# MBT42Q_CR2032_v01.net
KiCad netlist of a schematic drawn in EAGLE
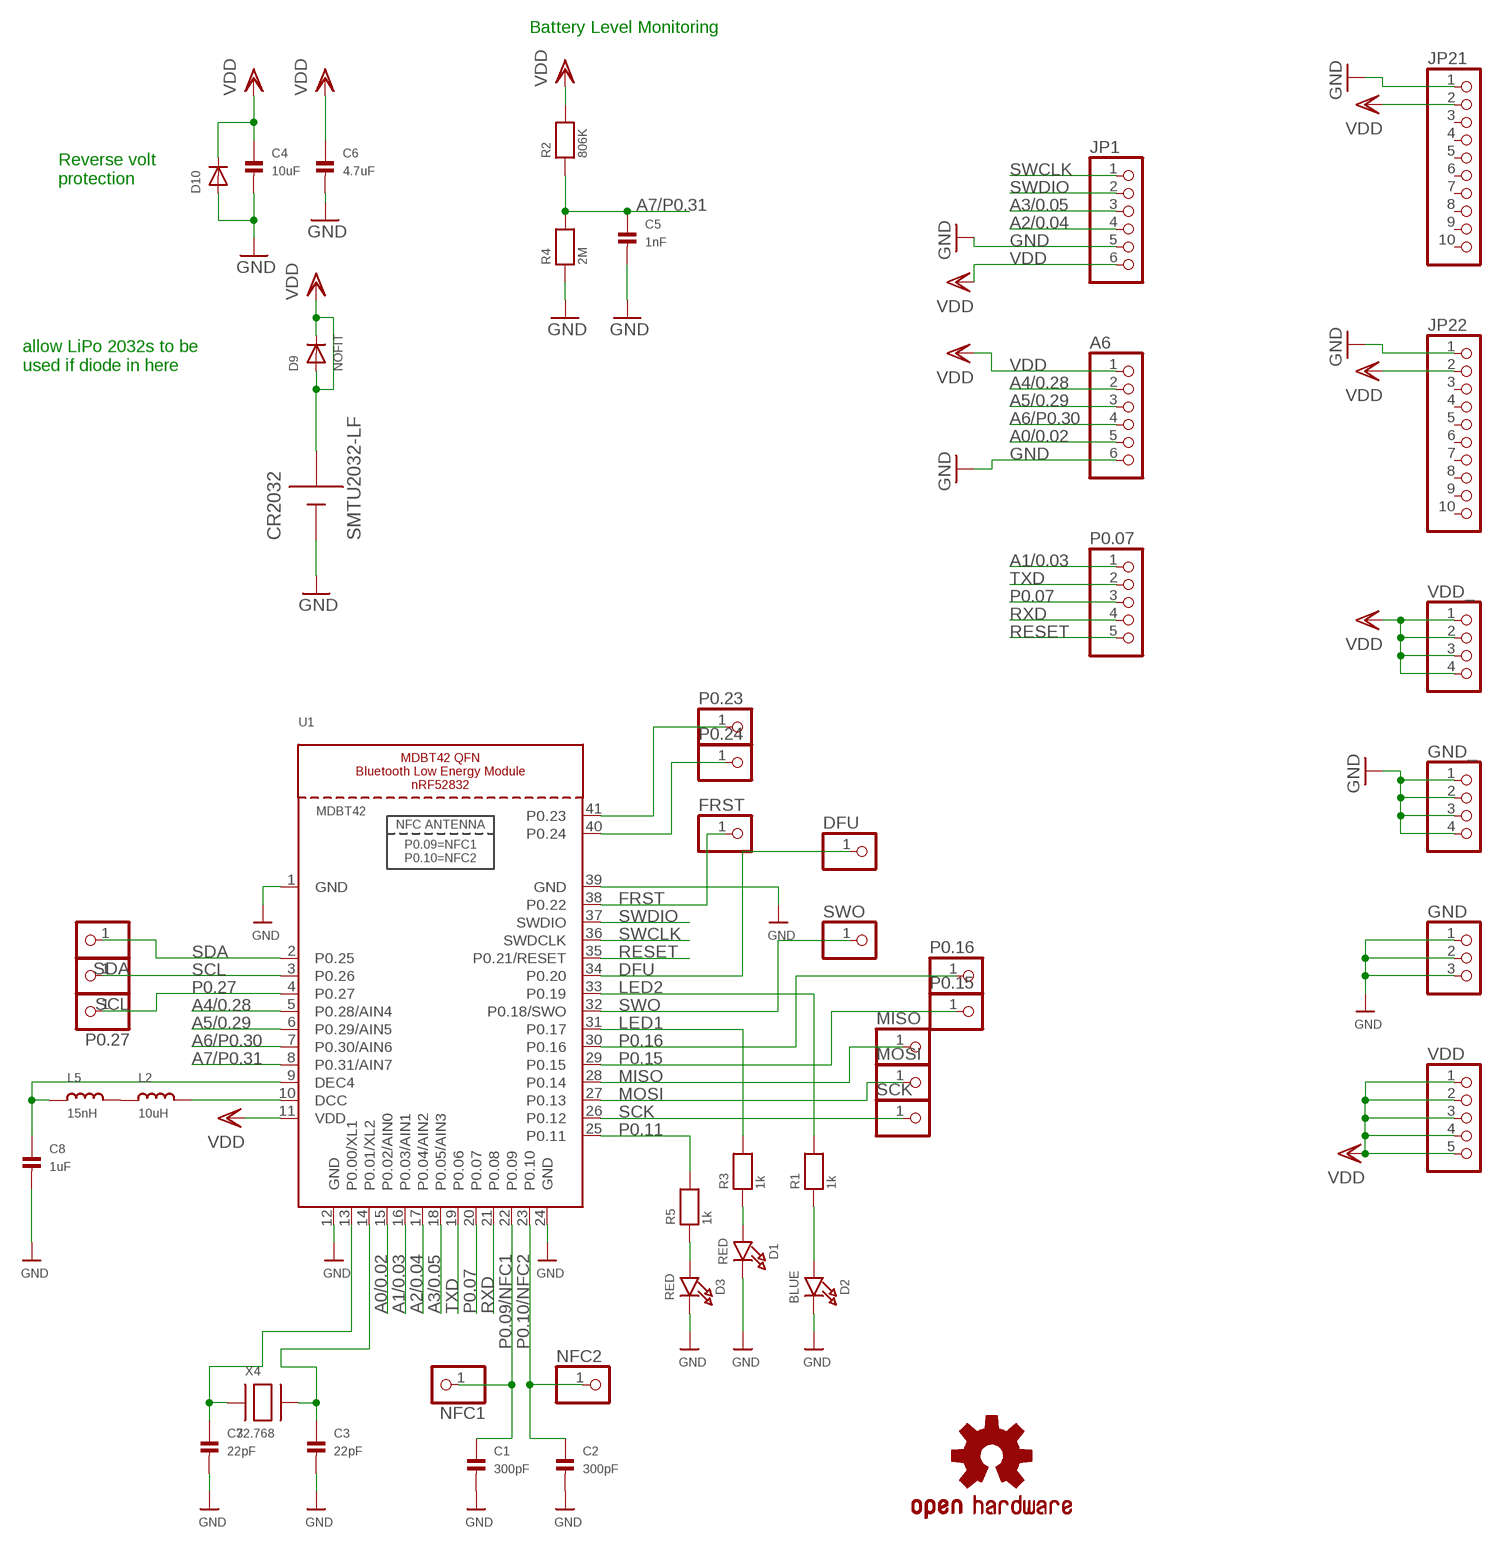
[diagram p0: schematic, sheet 1]

(export (version "E")
  (design (tool "Eeschema 10.0.6"))
  (components
    (comp (ref "A6")
      (value "HEADER-1X6ROUND")
      (footprint "eagle-import:1X06_ROUND")
      (libsource (lib "eagle-import") (part "HEADER-1X6ROUND"))
    )
    (comp (ref "C1")
      (value "300pF")
      (footprint "eagle-import:0805")
      (libsource (lib "eagle-import") (part "CAP_CERAMIC0805"))
    )
    (comp (ref "C2")
      (value "300pF")
      (footprint "eagle-import:0805")
      (libsource (lib "eagle-import") (part "CAP_CERAMIC0805"))
    )
    (comp (ref "C3")
      (value "22pF")
      (footprint "eagle-import:0805")
      (libsource (lib "eagle-import") (part "CAP_CERAMIC0805"))
    )
    (comp (ref "C4")
      (value "10uF")
      (footprint "eagle-import:0805")
      (libsource (lib "eagle-import") (part "CAP_CERAMIC0805"))
    )
    (comp (ref "C5")
      (value "1nF")
      (footprint "eagle-import:0805")
      (libsource (lib "eagle-import") (part "CAP_CERAMIC0805"))
    )
    (comp (ref "C6")
      (value "4.7uF")
      (footprint "eagle-import:0805")
      (libsource (lib "eagle-import") (part "CAP_CERAMIC0805"))
    )
    (comp (ref "C7")
      (value "22pF")
      (footprint "eagle-import:0805")
      (libsource (lib "eagle-import") (part "CAP_CERAMIC0805"))
    )
    (comp (ref "C8")
      (value "1uF")
      (footprint "eagle-import:0805")
      (libsource (lib "eagle-import") (part "CAP_CERAMIC0805"))
    )
    (comp (ref "CR2032")
      (value "SMTU2032-LF")
      (footprint "eagle-import:SMTU2032-LF")
      (libsource (lib "eagle-import") (part "SMTU2032-LF"))
    )
    (comp (ref "D1")
      (value "RED")
      (footprint "eagle-import:CHIPLED_0805_NOOUTLINE")
      (libsource (lib "eagle-import") (part "LED0805_NOOUTLINE"))
    )
    (comp (ref "D2")
      (value "BLUE")
      (footprint "eagle-import:CHIPLED_0805_NOOUTLINE")
      (libsource (lib "eagle-import") (part "LED0805_NOOUTLINE"))
    )
    (comp (ref "D3")
      (value "RED")
      (footprint "eagle-import:CHIPLED_0805_NOOUTLINE")
      (libsource (lib "eagle-import") (part "LED0805_NOOUTLINE"))
    )
    (comp (ref "D9")
      (value "NOFIT")
      (footprint "eagle-import:SOD-523")
      (libsource (lib "eagle-import") (part "DIODESOD-523"))
    )
    (comp (ref "D10")
      (value "DIODESOD-523")
      (footprint "eagle-import:SOD-523")
      (libsource (lib "eagle-import") (part "DIODESOD-523"))
    )
    (comp (ref "DFU")
      (value "HEADER-1X1ROUND")
      (footprint "eagle-import:1X01_ROUND")
      (libsource (lib "eagle-import") (part "HEADER-1X1ROUND"))
    )
    (comp (ref "FRST")
      (value "HEADER-1X1ROUND")
      (footprint "eagle-import:1X01_ROUND")
      (libsource (lib "eagle-import") (part "HEADER-1X1ROUND"))
    )
    (comp (ref "GND")
      (value "HEADER-1X3ROUND")
      (footprint "eagle-import:1X03_ROUND")
      (libsource (lib "eagle-import") (part "HEADER-1X3ROUND"))
    )
    (comp (ref "GND_")
      (value "HEADER-1X4ROUND")
      (footprint "eagle-import:1X04_ROUND")
      (libsource (lib "eagle-import") (part "HEADER-1X4ROUND"))
    )
    (comp (ref "JP1")
      (value "HEADER-1X6ROUND")
      (footprint "eagle-import:1X06_ROUND")
      (libsource (lib "eagle-import") (part "HEADER-1X6ROUND"))
    )
    (comp (ref "JP21")
      (value "HEADER-1X10ROUND")
      (footprint "eagle-import:1X10_ROUND")
      (libsource (lib "eagle-import") (part "HEADER-1X10ROUND"))
    )
    (comp (ref "JP22")
      (value "HEADER-1X10ROUND")
      (footprint "eagle-import:1X10_ROUND")
      (libsource (lib "eagle-import") (part "HEADER-1X10ROUND"))
    )
    (comp (ref "L2")
      (value "10uH")
      (footprint "eagle-import:_0805")
      (libsource (lib "eagle-import") (part "INDUCTOR_0805"))
    )
    (comp (ref "L5")
      (value "15nH")
      (footprint "eagle-import:_0805")
      (libsource (lib "eagle-import") (part "INDUCTOR_0805"))
    )
    (comp (ref "LOGO1")
      (value "OSHW-LOGOS")
      (footprint "eagle-import:OSHW-LOGO-S")
      (libsource (lib "eagle-import") (part "OSHW-LOGOS"))
    )
    (comp (ref "MISO")
      (value "HEADER-1X1ROUND")
      (footprint "eagle-import:1X01_ROUND")
      (libsource (lib "eagle-import") (part "HEADER-1X1ROUND"))
    )
    (comp (ref "MOSI")
      (value "HEADER-1X1ROUND")
      (footprint "eagle-import:1X01_ROUND")
      (libsource (lib "eagle-import") (part "HEADER-1X1ROUND"))
    )
    (comp (ref "NFC1")
      (value "HEADER-1X1ROUND")
      (footprint "eagle-import:1X01_ROUND")
      (libsource (lib "eagle-import") (part "HEADER-1X1ROUND"))
    )
    (comp (ref "NFC2")
      (value "HEADER-1X1ROUND")
      (footprint "eagle-import:1X01_ROUND")
      (libsource (lib "eagle-import") (part "HEADER-1X1ROUND"))
    )
    (comp (ref "P0.07")
      (value "HEADER-1X5ROUND")
      (footprint "eagle-import:1X05_ROUND")
      (libsource (lib "eagle-import") (part "HEADER-1X5ROUND"))
    )
    (comp (ref "P0.15")
      (value "HEADER-1X1ROUND")
      (footprint "eagle-import:1X01_ROUND")
      (libsource (lib "eagle-import") (part "HEADER-1X1ROUND"))
    )
    (comp (ref "P0.16")
      (value "HEADER-1X1ROUND")
      (footprint "eagle-import:1X01_ROUND")
      (libsource (lib "eagle-import") (part "HEADER-1X1ROUND"))
    )
    (comp (ref "P0.23")
      (value "HEADER-1X1ROUND")
      (footprint "eagle-import:1X01_ROUND")
      (libsource (lib "eagle-import") (part "HEADER-1X1ROUND"))
    )
    (comp (ref "P0.24")
      (value "HEADER-1X1ROUND")
      (footprint "eagle-import:1X01_ROUND")
      (libsource (lib "eagle-import") (part "HEADER-1X1ROUND"))
    )
    (comp (ref "P0.27")
      (value "HEADER-1X1ROUND")
      (footprint "eagle-import:1X01_ROUND")
      (libsource (lib "eagle-import") (part "HEADER-1X1ROUND"))
    )
    (comp (ref "R1")
      (value "1k")
      (footprint "eagle-import:0805")
      (libsource (lib "eagle-import") (part "RESISTOR0805"))
    )
    (comp (ref "R2")
      (value "806K")
      (footprint "eagle-import:0805")
      (libsource (lib "eagle-import") (part "RESISTOR0805"))
    )
    (comp (ref "R3")
      (value "1k")
      (footprint "eagle-import:0805")
      (libsource (lib "eagle-import") (part "RESISTOR0805"))
    )
    (comp (ref "R4")
      (value "2M")
      (footprint "eagle-import:0805")
      (libsource (lib "eagle-import") (part "RESISTOR0805"))
    )
    (comp (ref "R5")
      (value "1k")
      (footprint "eagle-import:0805")
      (libsource (lib "eagle-import") (part "RESISTOR0805"))
    )
    (comp (ref "SCK")
      (value "HEADER-1X1ROUND")
      (footprint "eagle-import:1X01_ROUND")
      (libsource (lib "eagle-import") (part "HEADER-1X1ROUND"))
    )
    (comp (ref "SCL")
      (value "HEADER-1X1ROUND")
      (footprint "eagle-import:1X01_ROUND")
      (libsource (lib "eagle-import") (part "HEADER-1X1ROUND"))
    )
    (comp (ref "SDA")
      (value "HEADER-1X1ROUND")
      (footprint "eagle-import:1X01_ROUND")
      (libsource (lib "eagle-import") (part "HEADER-1X1ROUND"))
    )
    (comp (ref "SWO")
      (value "HEADER-1X1ROUND")
      (footprint "eagle-import:1X01_ROUND")
      (libsource (lib "eagle-import") (part "HEADER-1X1ROUND"))
    )
    (comp (ref "U1")
      (value "MDBT42")
      (footprint "eagle-import:BLE_MODULE_RAYTAC_MDBT42")
      (libsource (lib "eagle-import") (part "NRF52832_MODULE_MDBT42"))
    )
    (comp (ref "VDD")
      (value "HEADER-1X5ROUND")
      (footprint "eagle-import:1X05_ROUND")
      (libsource (lib "eagle-import") (part "HEADER-1X5ROUND"))
    )
    (comp (ref "VDD_")
      (value "HEADER-1X4ROUND")
      (footprint "eagle-import:1X04_ROUND")
      (libsource (lib "eagle-import") (part "HEADER-1X4ROUND"))
    )
    (comp (ref "X4")
      (value "32.768")
      (footprint "eagle-import:XTAL3215")
      (libsource (lib "eagle-import") (part "XTAL-3.2X1.5"))
    )
  )
  (nets
    (net (code "1") (name "/A0{slash}0.02") (class "Default")
      (node (ref "A6") (pin "5") (pinfunction "5_5") (pintype "passive"))
      (node (ref "U1") (pin "15") (pinfunction "P0.02/AIN0_15") (pintype "bidirectional"))
    )
    (net (code "2") (name "/A1{slash}0.03") (class "Default")
      (node (ref "P0.07") (pin "1") (pinfunction "1_1") (pintype "passive"))
      (node (ref "U1") (pin "16") (pinfunction "P0.03/AIN1_16") (pintype "bidirectional"))
    )
    (net (code "3") (name "/A2{slash}0.04") (class "Default")
      (node (ref "JP1") (pin "4") (pinfunction "4_4") (pintype "passive"))
      (node (ref "U1") (pin "17") (pinfunction "P0.04/AIN2_17") (pintype "bidirectional"))
    )
    (net (code "4") (name "/A3{slash}0.05") (class "Default")
      (node (ref "JP1") (pin "3") (pinfunction "3_3") (pintype "passive"))
      (node (ref "U1") (pin "18") (pinfunction "P0.05/AIN3_18") (pintype "bidirectional"))
    )
    (net (code "5") (name "/A4{slash}0.28") (class "Default")
      (node (ref "A6") (pin "2") (pinfunction "2_2") (pintype "passive"))
      (node (ref "U1") (pin "5") (pinfunction "P0.28/AIN4_5") (pintype "bidirectional"))
    )
    (net (code "6") (name "/A5{slash}0.29") (class "Default")
      (node (ref "A6") (pin "3") (pinfunction "3_3") (pintype "passive"))
      (node (ref "U1") (pin "6") (pinfunction "P0.29/AIN5_6") (pintype "bidirectional"))
    )
    (net (code "7") (name "/A6{slash}P0.30") (class "Default")
      (node (ref "A6") (pin "4") (pinfunction "4_4") (pintype "passive"))
      (node (ref "U1") (pin "7") (pinfunction "P0.30/AIN6_7") (pintype "bidirectional"))
    )
    (net (code "8") (name "/A7{slash}P0.31") (class "Default")
      (node (ref "C5") (pin "1") (pinfunction "P$1_1") (pintype "passive"))
      (node (ref "R2") (pin "1") (pinfunction "1_1") (pintype "passive"))
      (node (ref "R4") (pin "2") (pinfunction "2_2") (pintype "passive"))
      (node (ref "U1") (pin "8") (pinfunction "P0.31/AIN7_8") (pintype "bidirectional"))
    )
    (net (code "9") (name "/DFU") (class "Default")
      (node (ref "DFU") (pin "1") (pinfunction "1_1") (pintype "passive"))
      (node (ref "U1") (pin "34") (pinfunction "P0.20_34") (pintype "bidirectional"))
    )
    (net (code "10") (name "/FRST") (class "Default")
      (node (ref "FRST") (pin "1") (pinfunction "1_1") (pintype "passive"))
      (node (ref "U1") (pin "38") (pinfunction "P0.22_38") (pintype "bidirectional"))
    )
    (net (code "11") (name "/LED1") (class "Default")
      (node (ref "R3") (pin "2") (pinfunction "2_2") (pintype "passive"))
      (node (ref "U1") (pin "31") (pinfunction "P0.17_31") (pintype "bidirectional"))
    )
    (net (code "12") (name "/LED2") (class "Default")
      (node (ref "R1") (pin "2") (pinfunction "2_2") (pintype "passive"))
      (node (ref "U1") (pin "33") (pinfunction "P0.19_33") (pintype "bidirectional"))
    )
    (net (code "13") (name "/MISO") (class "Default")
      (node (ref "MISO") (pin "1") (pinfunction "1_1") (pintype "passive"))
      (node (ref "U1") (pin "28") (pinfunction "P0.14_28") (pintype "bidirectional"))
    )
    (net (code "14") (name "/MOSI") (class "Default")
      (node (ref "MOSI") (pin "1") (pinfunction "1_1") (pintype "passive"))
      (node (ref "U1") (pin "27") (pinfunction "P0.13_27") (pintype "bidirectional"))
    )
    (net (code "15") (name "/P0.07") (class "Default")
      (node (ref "P0.07") (pin "3") (pinfunction "3_3") (pintype "passive"))
      (node (ref "U1") (pin "20") (pinfunction "P0.07_20") (pintype "bidirectional"))
    )
    (net (code "16") (name "/P0.09{slash}NFC1") (class "Default")
      (node (ref "C1") (pin "1") (pinfunction "P$1_1") (pintype "passive"))
      (node (ref "NFC1") (pin "1") (pinfunction "1_1") (pintype "passive"))
      (node (ref "U1") (pin "22") (pinfunction "P0.09_22") (pintype "bidirectional"))
    )
    (net (code "17") (name "/P0.10{slash}NFC2") (class "Default")
      (node (ref "C2") (pin "1") (pinfunction "P$1_1") (pintype "passive"))
      (node (ref "NFC2") (pin "1") (pinfunction "1_1") (pintype "passive"))
      (node (ref "U1") (pin "23") (pinfunction "P0.10_23") (pintype "bidirectional"))
    )
    (net (code "18") (name "/P0.11") (class "Default")
      (node (ref "R5") (pin "2") (pinfunction "2_2") (pintype "passive"))
      (node (ref "U1") (pin "25") (pinfunction "P0.11_25") (pintype "bidirectional"))
    )
    (net (code "19") (name "/P0.15") (class "Default")
      (node (ref "P0.15") (pin "1") (pinfunction "1_1") (pintype "passive"))
      (node (ref "U1") (pin "29") (pinfunction "P0.15_29") (pintype "bidirectional"))
    )
    (net (code "20") (name "/P0.16") (class "Default")
      (node (ref "P0.16") (pin "1") (pinfunction "1_1") (pintype "passive"))
      (node (ref "U1") (pin "30") (pinfunction "P0.16_30") (pintype "bidirectional"))
    )
    (net (code "21") (name "/P0.27") (class "Default")
      (node (ref "P0.27") (pin "1") (pinfunction "1_1") (pintype "passive"))
      (node (ref "U1") (pin "4") (pinfunction "P0.27_4") (pintype "bidirectional"))
    )
    (net (code "22") (name "/RESET") (class "Default")
      (node (ref "P0.07") (pin "5") (pinfunction "5_5") (pintype "passive"))
      (node (ref "U1") (pin "35") (pinfunction "P0.21/RESET_35") (pintype "bidirectional"))
    )
    (net (code "23") (name "/RXD") (class "Default")
      (node (ref "P0.07") (pin "4") (pinfunction "4_4") (pintype "passive"))
      (node (ref "U1") (pin "21") (pinfunction "P0.08_21") (pintype "bidirectional"))
    )
    (net (code "24") (name "/SCK") (class "Default")
      (node (ref "SCK") (pin "1") (pinfunction "1_1") (pintype "passive"))
      (node (ref "U1") (pin "26") (pinfunction "P0.12_26") (pintype "bidirectional"))
    )
    (net (code "25") (name "/SCL") (class "Default")
      (node (ref "SCL") (pin "1") (pinfunction "1_1") (pintype "passive"))
      (node (ref "U1") (pin "3") (pinfunction "P0.26_3") (pintype "bidirectional"))
    )
    (net (code "26") (name "/SDA") (class "Default")
      (node (ref "SDA") (pin "1") (pinfunction "1_1") (pintype "passive"))
      (node (ref "U1") (pin "2") (pinfunction "P0.25_2") (pintype "bidirectional"))
    )
    (net (code "27") (name "/SWCLK") (class "Default")
      (node (ref "JP1") (pin "1") (pinfunction "1_1") (pintype "passive"))
      (node (ref "U1") (pin "36") (pinfunction "SWDCLK_36") (pintype "bidirectional"))
    )
    (net (code "28") (name "/SWDIO") (class "Default")
      (node (ref "JP1") (pin "2") (pinfunction "2_2") (pintype "passive"))
      (node (ref "U1") (pin "37") (pinfunction "SWDIO_37") (pintype "bidirectional"))
    )
    (net (code "29") (name "/SWO") (class "Default")
      (node (ref "SWO") (pin "1") (pinfunction "1_1") (pintype "passive"))
      (node (ref "U1") (pin "32") (pinfunction "P0.18/SWO_32") (pintype "bidirectional"))
    )
    (net (code "30") (name "/TXD") (class "Default")
      (node (ref "P0.07") (pin "2") (pinfunction "2_2") (pintype "passive"))
      (node (ref "U1") (pin "19") (pinfunction "P0.06_19") (pintype "bidirectional"))
    )
    (net (code "31") (name "GND") (class "Default")
      (node (ref "A6") (pin "6") (pinfunction "6_6") (pintype "passive"))
      (node (ref "C1") (pin "2") (pinfunction "P$2_2") (pintype "passive"))
      (node (ref "C2") (pin "2") (pinfunction "P$2_2") (pintype "passive"))
      (node (ref "C3") (pin "2") (pinfunction "P$2_2") (pintype "passive"))
      (node (ref "C4") (pin "2") (pinfunction "P$2_2") (pintype "passive"))
      (node (ref "C5") (pin "2") (pinfunction "P$2_2") (pintype "passive"))
      (node (ref "C6") (pin "2") (pinfunction "P$2_2") (pintype "passive"))
      (node (ref "C7") (pin "2") (pinfunction "P$2_2") (pintype "passive"))
      (node (ref "C8") (pin "2") (pinfunction "P$2_2") (pintype "passive"))
      (node (ref "CR2032") (pin "P$2") (pinfunction "GND_P$2") (pintype "power_in"))
      (node (ref "D1") (pin "C") (pinfunction "C_C") (pintype "passive"))
      (node (ref "D10") (pin "A") (pinfunction "A_A") (pintype "passive"))
      (node (ref "D2") (pin "C") (pinfunction "C_C") (pintype "passive"))
      (node (ref "D3") (pin "C") (pinfunction "C_C") (pintype "passive"))
      (node (ref "GND") (pin "1") (pinfunction "1_1") (pintype "passive"))
      (node (ref "GND") (pin "2") (pinfunction "2_2") (pintype "passive"))
      (node (ref "GND") (pin "3") (pinfunction "3_3") (pintype "passive"))
      (node (ref "GND_") (pin "1") (pinfunction "1_1") (pintype "passive"))
      (node (ref "GND_") (pin "2") (pinfunction "2_2") (pintype "passive"))
      (node (ref "GND_") (pin "3") (pinfunction "3_3") (pintype "passive"))
      (node (ref "GND_") (pin "4") (pinfunction "4_4") (pintype "passive"))
      (node (ref "JP1") (pin "5") (pinfunction "5_5") (pintype "passive"))
      (node (ref "JP21") (pin "1") (pinfunction "1_1") (pintype "passive"))
      (node (ref "JP22") (pin "1") (pinfunction "1_1") (pintype "passive"))
      (node (ref "R4") (pin "1") (pinfunction "1_1") (pintype "passive"))
      (node (ref "U1") (pin "1") (pinfunction "GND_1") (pintype "bidirectional"))
      (node (ref "U1") (pin "12") (pinfunction "GND_12") (pintype "bidirectional"))
      (node (ref "U1") (pin "24") (pinfunction "GND_24") (pintype "bidirectional"))
      (node (ref "U1") (pin "39") (pinfunction "GND_39") (pintype "bidirectional"))
    )
    (net (code "32") (name "Net-(C3-P$1)") (class "Default")
      (node (ref "C3") (pin "1") (pinfunction "P$1_1") (pintype "passive"))
      (node (ref "U1") (pin "14") (pinfunction "P0.01/XL2_14") (pintype "bidirectional"))
      (node (ref "X4") (pin "P$2") (pinfunction "P$2_P$2") (pintype "bidirectional"))
    )
    (net (code "33") (name "Net-(C7-P$1)") (class "Default")
      (node (ref "C7") (pin "1") (pinfunction "P$1_1") (pintype "passive"))
      (node (ref "U1") (pin "13") (pinfunction "P0.00/XL1_13") (pintype "bidirectional"))
      (node (ref "X4") (pin "P$1") (pinfunction "P$1_P$1") (pintype "bidirectional"))
    )
    (net (code "34") (name "Net-(C8-P$1)") (class "Default")
      (node (ref "C8") (pin "1") (pinfunction "P$1_1") (pintype "passive"))
      (node (ref "L5") (pin "1") (pinfunction "1_1") (pintype "passive"))
      (node (ref "U1") (pin "9") (pinfunction "DEC4_9") (pintype "bidirectional"))
    )
    (net (code "35") (name "Net-(D1-PadA)") (class "Default")
      (node (ref "D1") (pin "A") (pinfunction "A_A") (pintype "passive"))
      (node (ref "R3") (pin "1") (pinfunction "1_1") (pintype "passive"))
    )
    (net (code "36") (name "Net-(D2-PadA)") (class "Default")
      (node (ref "D2") (pin "A") (pinfunction "A_A") (pintype "passive"))
      (node (ref "R1") (pin "1") (pinfunction "1_1") (pintype "passive"))
    )
    (net (code "37") (name "Net-(D3-PadA)") (class "Default")
      (node (ref "D3") (pin "A") (pinfunction "A_A") (pintype "passive"))
      (node (ref "R5") (pin "1") (pinfunction "1_1") (pintype "passive"))
    )
    (net (code "38") (name "Net-(L2-Pad1)") (class "Default")
      (node (ref "L2") (pin "1") (pinfunction "1_1") (pintype "passive"))
      (node (ref "L5") (pin "2") (pinfunction "2_2") (pintype "passive"))
    )
    (net (code "39") (name "Net-(U1-DCC)") (class "Default")
      (node (ref "L2") (pin "2") (pinfunction "2_2") (pintype "passive"))
      (node (ref "U1") (pin "10") (pinfunction "DCC_10") (pintype "bidirectional"))
    )
    (net (code "40") (name "Net-(U1-P0.23)") (class "Default")
      (node (ref "P0.23") (pin "1") (pinfunction "1_1") (pintype "passive"))
      (node (ref "U1") (pin "41") (pinfunction "P0.23_41") (pintype "bidirectional"))
    )
    (net (code "41") (name "Net-(U1-P0.24)") (class "Default")
      (node (ref "P0.24") (pin "1") (pinfunction "1_1") (pintype "passive"))
      (node (ref "U1") (pin "40") (pinfunction "P0.24_40") (pintype "bidirectional"))
    )
    (net (code "42") (name "VDD") (class "Default")
      (node (ref "A6") (pin "1") (pinfunction "1_1") (pintype "passive"))
      (node (ref "C4") (pin "1") (pinfunction "P$1_1") (pintype "passive"))
      (node (ref "C6") (pin "1") (pinfunction "P$1_1") (pintype "passive"))
      (node (ref "CR2032") (pin "P$1") (pinfunction "3V_P$1") (pintype "power_in"))
      (node (ref "D10") (pin "K") (pinfunction "C_K") (pintype "passive"))
      (node (ref "D9") (pin "A") (pinfunction "A_A") (pintype "passive"))
      (node (ref "D9") (pin "K") (pinfunction "C_K") (pintype "passive"))
      (node (ref "JP1") (pin "6") (pinfunction "6_6") (pintype "passive"))
      (node (ref "JP21") (pin "2") (pinfunction "2_2") (pintype "passive"))
      (node (ref "JP22") (pin "2") (pinfunction "2_2") (pintype "passive"))
      (node (ref "R2") (pin "2") (pinfunction "2_2") (pintype "passive"))
      (node (ref "U1") (pin "11") (pinfunction "VDD_11") (pintype "bidirectional"))
      (node (ref "VDD") (pin "1") (pinfunction "1_1") (pintype "passive"))
      (node (ref "VDD") (pin "2") (pinfunction "2_2") (pintype "passive"))
      (node (ref "VDD") (pin "3") (pinfunction "3_3") (pintype "passive"))
      (node (ref "VDD") (pin "4") (pinfunction "4_4") (pintype "passive"))
      (node (ref "VDD") (pin "5") (pinfunction "5_5") (pintype "passive"))
      (node (ref "VDD_") (pin "1") (pinfunction "1_1") (pintype "passive"))
      (node (ref "VDD_") (pin "2") (pinfunction "2_2") (pintype "passive"))
      (node (ref "VDD_") (pin "3") (pinfunction "3_3") (pintype "passive"))
      (node (ref "VDD_") (pin "4") (pinfunction "4_4") (pintype "passive"))
    )
    (net (code "43") (name "unconnected-(JP21-Pad3)") (class "Default")
      (node (ref "JP21") (pin "3") (pinfunction "3_3") (pintype "passive"))
    )
    (net (code "44") (name "unconnected-(JP21-Pad4)") (class "Default")
      (node (ref "JP21") (pin "4") (pinfunction "4_4") (pintype "passive"))
    )
    (net (code "45") (name "unconnected-(JP21-Pad5)") (class "Default")
      (node (ref "JP21") (pin "5") (pinfunction "5_5") (pintype "passive"))
    )
    (net (code "46") (name "unconnected-(JP21-Pad6)") (class "Default")
      (node (ref "JP21") (pin "6") (pinfunction "6_6") (pintype "passive"))
    )
    (net (code "47") (name "unconnected-(JP21-Pad7)") (class "Default")
      (node (ref "JP21") (pin "7") (pinfunction "7_7") (pintype "passive"))
    )
    (net (code "48") (name "unconnected-(JP21-Pad8)") (class "Default")
      (node (ref "JP21") (pin "8") (pinfunction "8_8") (pintype "passive"))
    )
    (net (code "49") (name "unconnected-(JP21-Pad9)") (class "Default")
      (node (ref "JP21") (pin "9") (pinfunction "9_9") (pintype "passive"))
    )
    (net (code "50") (name "unconnected-(JP21-Pad10)") (class "Default")
      (node (ref "JP21") (pin "10") (pinfunction "10_10") (pintype "passive"))
    )
    (net (code "51") (name "unconnected-(JP22-Pad3)") (class "Default")
      (node (ref "JP22") (pin "3") (pinfunction "3_3") (pintype "passive"))
    )
    (net (code "52") (name "unconnected-(JP22-Pad4)") (class "Default")
      (node (ref "JP22") (pin "4") (pinfunction "4_4") (pintype "passive"))
    )
    (net (code "53") (name "unconnected-(JP22-Pad5)") (class "Default")
      (node (ref "JP22") (pin "5") (pinfunction "5_5") (pintype "passive"))
    )
    (net (code "54") (name "unconnected-(JP22-Pad6)") (class "Default")
      (node (ref "JP22") (pin "6") (pinfunction "6_6") (pintype "passive"))
    )
    (net (code "55") (name "unconnected-(JP22-Pad7)") (class "Default")
      (node (ref "JP22") (pin "7") (pinfunction "7_7") (pintype "passive"))
    )
    (net (code "56") (name "unconnected-(JP22-Pad8)") (class "Default")
      (node (ref "JP22") (pin "8") (pinfunction "8_8") (pintype "passive"))
    )
    (net (code "57") (name "unconnected-(JP22-Pad9)") (class "Default")
      (node (ref "JP22") (pin "9") (pinfunction "9_9") (pintype "passive"))
    )
    (net (code "58") (name "unconnected-(JP22-Pad10)") (class "Default")
      (node (ref "JP22") (pin "10") (pinfunction "10_10") (pintype "passive"))
    )
  )
)
